# main.net
KiCad netlist of a schematic drawn in Altium Designer
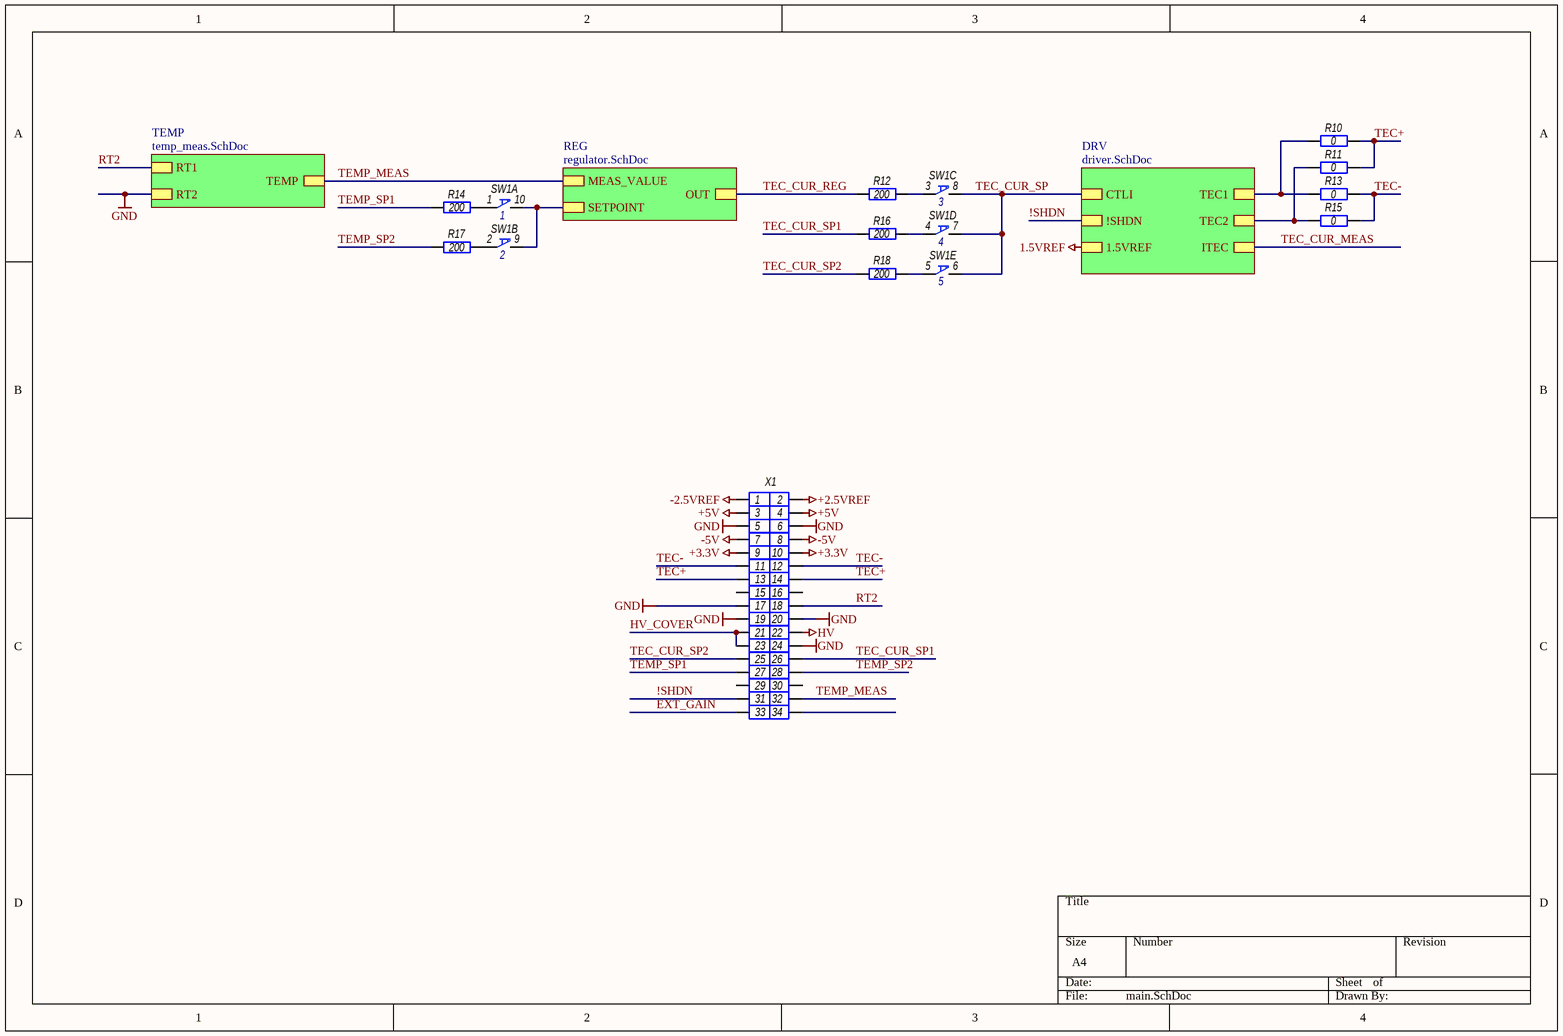
[diagram p0: main.SchDoc]

(export (version "E")
  (design (tool "Eeschema 10.0.6"))
  (components
    (comp (ref "R10")
      (value "0")
      (footprint "RES_0805")
      (description "Резистор")
      (libsource (lib "SCH_LIB") (part "Resisitor"))
    )
    (comp (ref "R11")
      (value "0")
      (footprint "RES_0805")
      (description "Резистор")
      (libsource (lib "SCH_LIB") (part "Resisitor"))
    )
    (comp (ref "R12")
      (value "200")
      (footprint "RES_0603")
      (description "Резистор")
      (libsource (lib "SCH_LIB") (part "Resisitor"))
    )
    (comp (ref "R13")
      (value "0")
      (footprint "RES_0805")
      (description "Резистор")
      (libsource (lib "SCH_LIB") (part "Resisitor"))
    )
    (comp (ref "R14")
      (value "200")
      (footprint "RES_0603")
      (description "Резистор")
      (libsource (lib "SCH_LIB") (part "Resisitor"))
    )
    (comp (ref "R15")
      (value "0")
      (footprint "RES_0805")
      (description "Резистор")
      (libsource (lib "SCH_LIB") (part "Resisitor"))
    )
    (comp (ref "R16")
      (value "200")
      (footprint "RES_0603")
      (description "Резистор")
      (libsource (lib "SCH_LIB") (part "Resisitor"))
    )
    (comp (ref "R17")
      (value "200")
      (footprint "RES_0603")
      (description "Резистор")
      (libsource (lib "SCH_LIB") (part "Resisitor"))
    )
    (comp (ref "R18")
      (value "200")
      (footprint "RES_0603")
      (description "Резистор")
      (libsource (lib "SCH_LIB") (part "Resisitor"))
    )
    (comp (ref "SW1")
      (value "?")
      (footprint "SWD1-5")
      (description "Переключатель 2 группы прямой:\r\nSWD1-5;\r\nDS1040-05RN;\r\nDS1040-05BN;\r\nBD05")
      (libsource (lib "SCH_LIB") (part "SWD1-5"))
    )
    (comp (ref "X1") (value "?") (footprint "BH-34") (libsource (lib "SCH_LIB") (part "Connector 17x2")))
  )
  (nets
    (net (code "1") (name "+2.5VREF") (class "Default")
      (node (ref "X1") (pin "2") (pinfunction "2_2") (pintype "passive"))
    )
    (net (code "2") (name "+3.3V") (class "Default")
      (node (ref "X1") (pin "10") (pinfunction "10_10") (pintype "passive"))
      (node (ref "X1") (pin "9") (pinfunction "9_9") (pintype "passive"))
    )
    (net (code "3") (name "+5V") (class "Default")
      (node (ref "X1") (pin "3") (pinfunction "3_3") (pintype "passive"))
      (node (ref "X1") (pin "4") (pinfunction "4_4") (pintype "passive"))
    )
    (net (code "4") (name "-2.5VREF") (class "Default")
      (node (ref "X1") (pin "1") (pinfunction "1_1") (pintype "passive"))
    )
    (net (code "5") (name "-5V") (class "Default")
      (node (ref "X1") (pin "7") (pinfunction "7_7") (pintype "passive"))
      (node (ref "X1") (pin "8") (pinfunction "8_8") (pintype "passive"))
    )
    (net (code "6") (name "/!SHDN") (class "Default")
      (node (ref "X1") (pin "31") (pinfunction "31_31") (pintype "passive"))
    )
    (net (code "7") (name "/EXT_GAIN") (class "Default")
      (node (ref "X1") (pin "33") (pinfunction "33_33") (pintype "passive"))
    )
    (net (code "8") (name "/HV_COVER") (class "Default")
      (node (ref "X1") (pin "21") (pinfunction "21_21") (pintype "passive"))
      (node (ref "X1") (pin "23") (pinfunction "23_23") (pintype "passive"))
    )
    (net (code "9") (name "/RT2") (class "Default")
      (node (ref "X1") (pin "18") (pinfunction "18_18") (pintype "passive"))
    )
    (net (code "10") (name "/SETPOINT") (class "Default")
      (node (ref "SW1") (pin "10") (pintype "passive"))
      (node (ref "SW1") (pin "9") (pintype "passive"))
    )
    (net (code "11") (name "/TEC+") (class "Default")
      (node (ref "R10") (pin "2") (pinfunction "2_2") (pintype "passive"))
      (node (ref "R11") (pin "2") (pinfunction "2_2") (pintype "passive"))
      (node (ref "X1") (pin "13") (pinfunction "13_13") (pintype "passive"))
      (node (ref "X1") (pin "14") (pinfunction "14_14") (pintype "passive"))
    )
    (net (code "12") (name "/TEC-") (class "Default")
      (node (ref "R13") (pin "2") (pinfunction "2_2") (pintype "passive"))
      (node (ref "R15") (pin "2") (pinfunction "2_2") (pintype "passive"))
      (node (ref "X1") (pin "11") (pinfunction "11_11") (pintype "passive"))
      (node (ref "X1") (pin "12") (pinfunction "12_12") (pintype "passive"))
    )
    (net (code "13") (name "/TEC1") (class "Default")
      (node (ref "R10") (pin "1") (pinfunction "1_1") (pintype "passive"))
      (node (ref "R13") (pin "1") (pinfunction "1_1") (pintype "passive"))
    )
    (net (code "14") (name "/TEC2") (class "Default")
      (node (ref "R11") (pin "1") (pinfunction "1_1") (pintype "passive"))
      (node (ref "R15") (pin "1") (pinfunction "1_1") (pintype "passive"))
    )
    (net (code "16") (name "/TEC_CUR_REG") (class "Default")
      (node (ref "R12") (pin "1") (pinfunction "1_1") (pintype "passive"))
    )
    (net (code "17") (name "/TEC_CUR_SP") (class "Default")
      (node (ref "SW1") (pin "6") (pintype "passive"))
      (node (ref "SW1") (pin "7") (pintype "passive"))
      (node (ref "SW1") (pin "8") (pintype "passive"))
    )
    (net (code "18") (name "/TEC_CUR_SP1") (class "Default")
      (node (ref "R16") (pin "1") (pinfunction "1_1") (pintype "passive"))
      (node (ref "X1") (pin "26") (pinfunction "26_26") (pintype "passive"))
    )
    (net (code "19") (name "/TEC_CUR_SP2") (class "Default")
      (node (ref "R18") (pin "1") (pinfunction "1_1") (pintype "passive"))
      (node (ref "X1") (pin "25") (pinfunction "25_25") (pintype "passive"))
    )
    (net (code "20") (name "/TEMP_MEAS") (class "Default")
      (node (ref "X1") (pin "32") (pinfunction "32_32") (pintype "passive"))
    )
    (net (code "21") (name "/TEMP_SP1") (class "Default")
      (node (ref "R14") (pin "1") (pinfunction "1_1") (pintype "passive"))
      (node (ref "X1") (pin "27") (pinfunction "27_27") (pintype "passive"))
    )
    (net (code "22") (name "/TEMP_SP2") (class "Default")
      (node (ref "R17") (pin "1") (pinfunction "1_1") (pintype "passive"))
      (node (ref "X1") (pin "28") (pinfunction "28_28") (pintype "passive"))
    )
    (net (code "24") (name "GND") (class "Default")
      (node (ref "X1") (pin "17") (pinfunction "17_17") (pintype "passive"))
      (node (ref "X1") (pin "19") (pinfunction "19_19") (pintype "passive"))
      (node (ref "X1") (pin "20") (pinfunction "20_20") (pintype "passive"))
      (node (ref "X1") (pin "24") (pinfunction "24_24") (pintype "passive"))
      (node (ref "X1") (pin "5") (pinfunction "5_5") (pintype "passive"))
      (node (ref "X1") (pin "6") (pinfunction "6_6") (pintype "passive"))
    )
    (net (code "25") (name "HV") (class "Default")
      (node (ref "X1") (pin "22") (pinfunction "22_22") (pintype "passive"))
    )
    (net (code "26") (name "Net-(R12-Pad2)") (class "Default")
      (node (ref "R12") (pin "2") (pinfunction "2_2") (pintype "passive"))
      (node (ref "SW1") (pin "3") (pintype "passive"))
    )
    (net (code "27") (name "Net-(R14-Pad2)") (class "Default")
      (node (ref "R14") (pin "2") (pinfunction "2_2") (pintype "passive"))
      (node (ref "SW1") (pin "1") (pintype "passive"))
    )
    (net (code "28") (name "Net-(R16-Pad2)") (class "Default")
      (node (ref "R16") (pin "2") (pinfunction "2_2") (pintype "passive"))
      (node (ref "SW1") (pin "4") (pintype "passive"))
    )
    (net (code "29") (name "Net-(R17-Pad2)") (class "Default")
      (node (ref "R17") (pin "2") (pinfunction "2_2") (pintype "passive"))
      (node (ref "SW1") (pin "2") (pintype "passive"))
    )
    (net (code "30") (name "Net-(R18-Pad2)") (class "Default")
      (node (ref "R18") (pin "2") (pinfunction "2_2") (pintype "passive"))
      (node (ref "SW1") (pin "5") (pintype "passive"))
    )
    (net (code "31") (name "unconnected-(X1-Pad15)") (class "Default")
      (node (ref "X1") (pin "15") (pinfunction "15_15") (pintype "passive"))
    )
    (net (code "32") (name "unconnected-(X1-Pad16)") (class "Default")
      (node (ref "X1") (pin "16") (pinfunction "16_16") (pintype "passive"))
    )
    (net (code "33") (name "unconnected-(X1-Pad29)") (class "Default")
      (node (ref "X1") (pin "29") (pinfunction "29_29") (pintype "passive"))
    )
    (net (code "34") (name "unconnected-(X1-Pad30)") (class "Default")
      (node (ref "X1") (pin "30") (pinfunction "30_30") (pintype "passive"))
    )
    (net (code "35") (name "unconnected-(X1-Pad34)") (class "Default")
      (node (ref "X1") (pin "34") (pinfunction "34_34") (pintype "passive"))
    )
  )
)
